# SCHE_BUZZ.net
KiCad netlist of a schematic drawn in Altium Designer
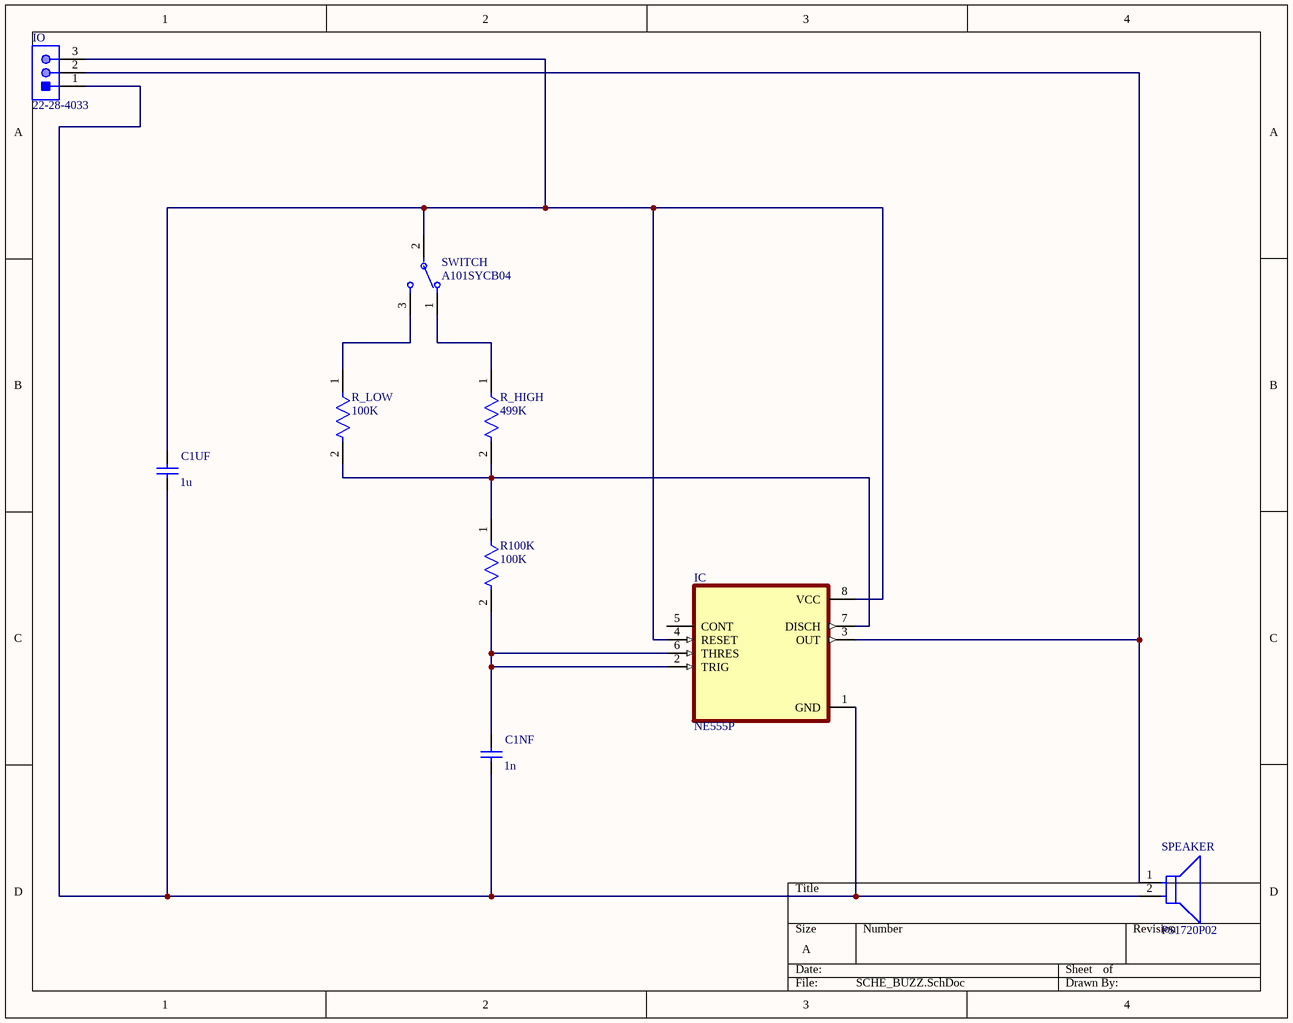
[diagram p0: SCHE_BUZZ.SchDoc]

(export (version "E")
  (design (tool "Eeschema 10.0.6"))
  (components
    (comp (ref "C1NF")
      (value "1n")
      (footprint "KEMT-C330C105M5U5TA")
      (description "Ceramic Capacitor, 1 uF, +/- 20%, 50 V, -10 to 85 degC, 2-Pin THD, RoHS, Bulk")
      (fields (field (name "TOLERANCE") "±20%") (field (name "MANUFACTURER") "Kemet"))
      (libsource (lib "Altium Content Vault") (part "CAP-NP-2"))
    )
    (comp (ref "C1UF")
      (value "1u")
      (footprint "KEMT-C330C105M5U5TA")
      (description "Ceramic Capacitor, 1 uF, +/- 20%, 50 V, -10 to 85 degC, 2-Pin THD, RoHS, Bulk")
      (fields (field (name "TOLERANCE") "±20%") (field (name "MANUFACTURER") "Kemet"))
      (libsource (lib "Altium Content Vault") (part "CAP-NP-2"))
    )
    (comp (ref "IC")
      (value "NE555P")
      (footprint "DIP794W45P254L959H508Q8")
      (libsource (lib "NE555P") (part "NE555P"))
    )
    (comp (ref "IO")
      (value "22-28-4033")
      (footprint "MOLX-22-28-4033_V")
      (description "Male Header, Pitch 2.54 mm, 1 x 3 Position, Height 8.38 mm, Tail Length 3.18 mm, RoHS, Bulk")
      (fields (field (name "MANUFACTURER") "Molex"))
      (libsource (lib "Altium Content Vault") (part "CN-1P-M-R3"))
    )
    (comp (ref "R100K")
      (value "100K")
      (footprint "FP-AC05000003909JAC00-0")
      (fields
        (field (name "OCTOPART") "https://octopart.com/ac05000003909jac00-vishay-39746279")
        (field (name "MANUFACTURER") "Vishay")
        (field (name "TOLERANCE") "5%")
      )
      (libsource (lib "Altium Content Vault") (part "1029c3af85768c4190bb7ad29bc67b5"))
    )
    (comp (ref "R_HIGH")
      (value "499K")
      (footprint "FP-AC05000003909JAC00-0")
      (fields
        (field (name "OCTOPART") "https://octopart.com/ac05000003909jac00-vishay-39746279")
        (field (name "MANUFACTURER") "Vishay")
        (field (name "TOLERANCE") "5%")
      )
      (libsource (lib "Altium Content Vault") (part "1029c3af85768c4190bb7ad29bc67b5"))
    )
    (comp (ref "R_LOW")
      (value "100K")
      (footprint "FP-AC05000003909JAC00-0")
      (fields
        (field (name "OCTOPART") "https://octopart.com/ac05000003909jac00-vishay-39746279")
        (field (name "MANUFACTURER") "Vishay")
        (field (name "TOLERANCE") "5%")
      )
      (libsource (lib "Altium Content Vault") (part "1029c3af85768c4190bb7ad29bc67b5"))
    )
    (comp (ref "SPEAKER")
      (value "PS1720P02")
      (footprint "FP-PS1720P02-MFG")
      (description "AUDIO PIEZO TRANSDUCER 30V TH")
      (fields
        (field (name "OCTOPART") "https://octopart.com/ps1720p02-tdk-154429")
        (field (name "MANUFACTURER") "TDK Corporation")
      )
      (libsource (lib "Altium Content Vault") (part "5f581d31613f872430949aa526fd155"))
    )
    (comp (ref "SWITCH")
      (value "A101SYCB04")
      (footprint "FP-A101SYCB04-MFG")
      (description "SWITCH TOGGLE SPDT 0.4VA 20V")
      (libsource (lib "Altium Content Vault") (part "52c419afdc2a387c7d548259a9aeefb"))
    )
  )
  (nets
    (net (code "1") (name "Net-(IC-DISCH)") (class "Default")
      (node (ref "IC") (pin "7") (pinfunction "DISCH_7") (pintype "output"))
      (node (ref "R100K") (pin "1") (pinfunction "1_1") (pintype "passive"))
      (node (ref "R_HIGH") (pin "2") (pinfunction "2_2") (pintype "passive"))
      (node (ref "R_LOW") (pin "2") (pinfunction "2_2") (pintype "passive"))
    )
    (net (code "2") (name "Net-(IC-GND)") (class "Default")
      (node (ref "C1NF") (pin "2") (pinfunction "2_2") (pintype "passive"))
      (node (ref "C1UF") (pin "2") (pinfunction "2_2") (pintype "passive"))
      (node (ref "IC") (pin "1") (pinfunction "GND_1") (pintype "power_in"))
      (node (ref "IO") (pin "1") (pinfunction "1_1") (pintype "passive"))
      (node (ref "SPEAKER") (pin "2") (pinfunction "2_2") (pintype "passive"))
    )
    (net (code "3") (name "Net-(IC-OUT)") (class "Default")
      (node (ref "IC") (pin "3") (pinfunction "OUT_3") (pintype "output"))
      (node (ref "IO") (pin "2") (pinfunction "2_2") (pintype "passive"))
      (node (ref "SPEAKER") (pin "1") (pinfunction "1_1") (pintype "passive"))
    )
    (net (code "4") (name "Net-(IC-RESET)") (class "Default")
      (node (ref "C1UF") (pin "1") (pinfunction "1_1") (pintype "passive"))
      (node (ref "IC") (pin "4") (pinfunction "RESET_4") (pintype "input"))
      (node (ref "IC") (pin "8") (pinfunction "VCC_8") (pintype "power_in"))
      (node (ref "IO") (pin "3") (pinfunction "3_3") (pintype "passive"))
      (node (ref "SWITCH") (pin "2") (pinfunction "2_2") (pintype "passive"))
    )
    (net (code "5") (name "Net-(IC-THRES)") (class "Default")
      (node (ref "C1NF") (pin "1") (pinfunction "1_1") (pintype "passive"))
      (node (ref "IC") (pin "2") (pinfunction "TRIG_2") (pintype "input"))
      (node (ref "IC") (pin "6") (pinfunction "THRES_6") (pintype "input"))
      (node (ref "R100K") (pin "2") (pinfunction "2_2") (pintype "passive"))
    )
    (net (code "6") (name "Net-(R_HIGH-Pad1)") (class "Default")
      (node (ref "R_HIGH") (pin "1") (pinfunction "1_1") (pintype "passive"))
      (node (ref "SWITCH") (pin "1") (pinfunction "1_1") (pintype "passive"))
    )
    (net (code "7") (name "Net-(R_LOW-Pad1)") (class "Default")
      (node (ref "R_LOW") (pin "1") (pinfunction "1_1") (pintype "passive"))
      (node (ref "SWITCH") (pin "3") (pinfunction "3_3") (pintype "passive"))
    )
    (net (code "8") (name "unconnected-(IC-CONT-Pad5)") (class "Default")
      (node (ref "IC") (pin "5") (pinfunction "CONT_5") (pintype "passive"))
    )
  )
)
